# Connectors.net
KiCad netlist of a schematic drawn in Altium Designer
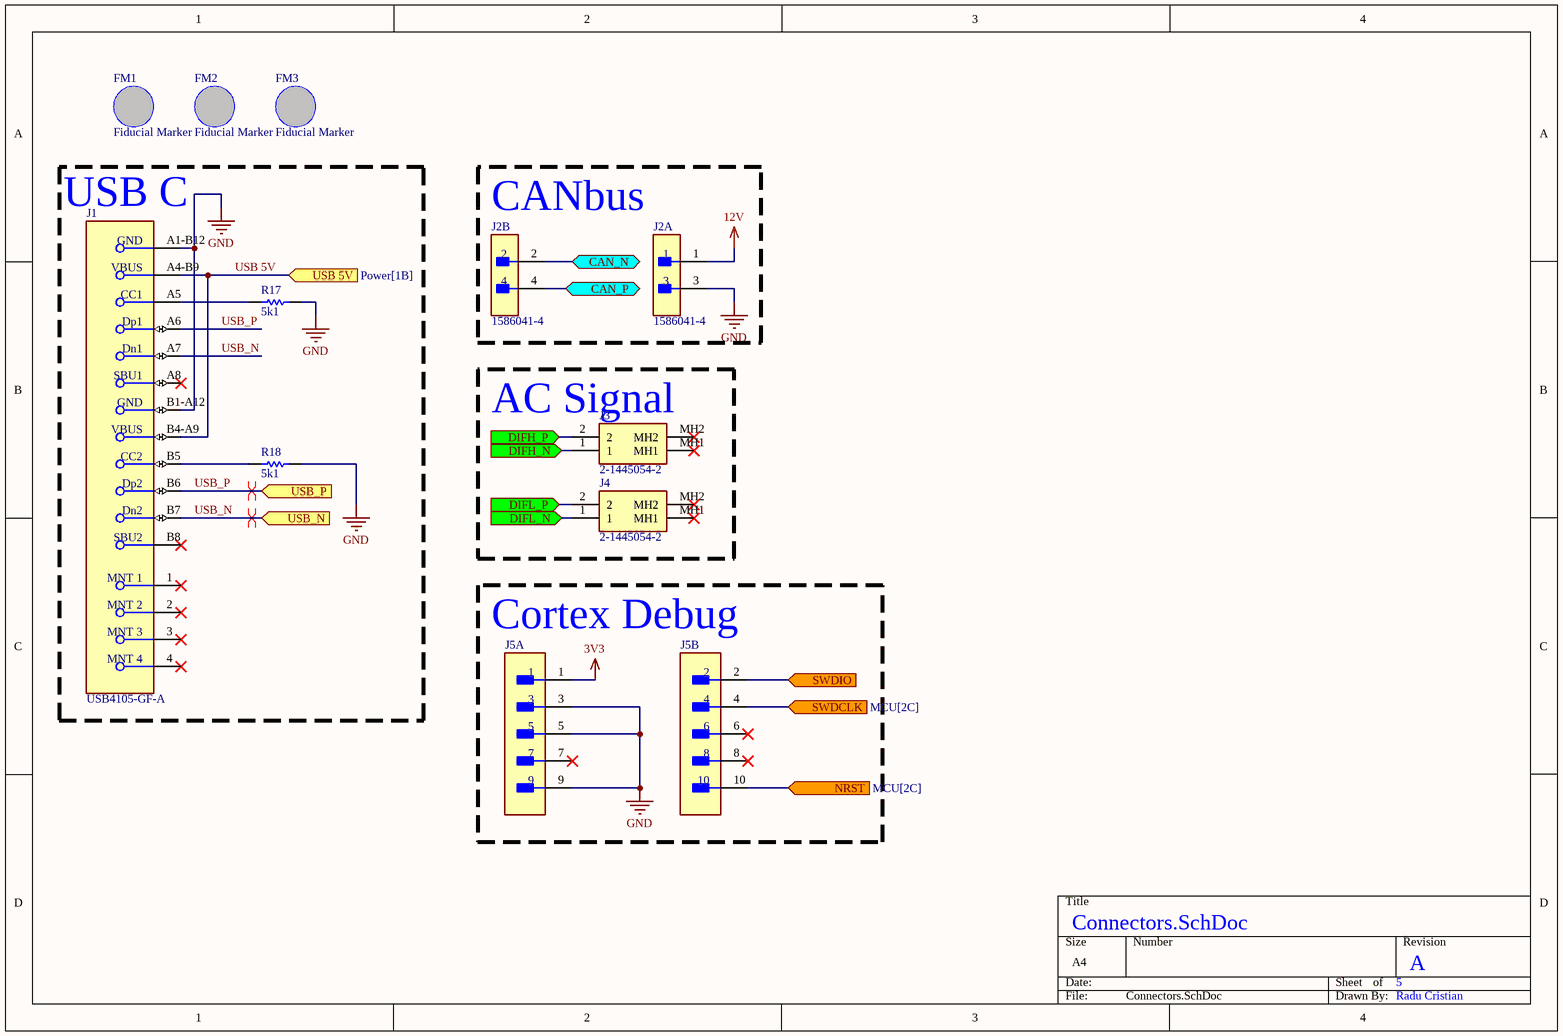
[diagram p0: Connectors.SchDoc]

(export (version "E")
  (design (tool "Eeschema 10.0.6"))
  (components
    (comp (ref "FM1")
      (value "Fiducial Marker")
      (footprint "Fiducial Marker-Footprint-1")
      (description "fancy style")
      (libsource (lib "ART-TU Cluj-Napoca") (part "FM?"))
    )
    (comp (ref "FM2")
      (value "Fiducial Marker")
      (footprint "Fiducial Marker-Footprint-1")
      (description "fancy style")
      (libsource (lib "ART-TU Cluj-Napoca") (part "FM?"))
    )
    (comp (ref "FM3")
      (value "Fiducial Marker")
      (footprint "Fiducial Marker-Footprint-1")
      (description "fancy style")
      (libsource (lib "ART-TU Cluj-Napoca") (part "FM?"))
    )
    (comp (ref "J1")
      (value "USB4105-GF-A")
      (footprint "FP-USB4105-GF-A-MFG")
      (description "CONN RCPT USB2.0 TYPEC 5A")
      (fields
        (field (name "MANUFACTURER") "GCT")
        (field (name "OCTOPART") "https://octopart.com/usb4105-gf-a-gct-106627878")
      )
      (libsource (lib "Altium Content Vault") (part "e7c17a616881a82b79941196b4bec10"))
    )
    (comp (ref "J2")
      (value "1586041-4")
      (footprint "FP-1586041-4-MFG")
      (description "CONN HEADER R/A 4POS 4.2MM")
      (fields
        (field (name "MANUFACTURER") "TE")
        (field (name "OCTOPART") "https://octopart.com/1586041-4-te+connectivity-46506786")
      )
      (libsource (lib "Altium Content Vault") (part "47a5dc621420b5f0973fcecc640382d"))
    )
    (comp (ref "J3")
      (value "2-1445054-2")
      (footprint "SamacSys:214450542")
      (description "Connector")
      (fields (field (name "MOUSER PART NUMBER") "571-2-1445054-2"))
      (libsource (lib "*") (part "2-1445054-2"))
    )
    (comp (ref "J4")
      (value "2-1445054-2")
      (footprint "SamacSys:214450542")
      (description "Connector")
      (fields (field (name "MOUSER PART NUMBER") "571-2-1445054-2"))
      (libsource (lib "*") (part "2-1445054-2"))
    )
    (comp (ref "J5")
      (value "FTSH-105-01-L-DV-K-P-TR")
      (footprint "FP-FTSH-105-01-L-DV-K-P-T-MFG")
      (description "CONN HEADER SMD 10POS 1.27MM")
      (libsource (lib "Altium Content Vault") (part "544f42128f4185dcb88ce1ce9bf1982"))
    )
    (comp (ref "R17")
      (value "RK73H2ATTD5101F")
      (footprint "RESC2013X60X30NL20T20")
      (fields (field (name "MANUFACTURER") "KOA Speer") (field (name "PARAMETER 1") "5k1"))
      (libsource (lib "Altium Content Vault") (part "RES"))
    )
    (comp (ref "R18")
      (value "RK73H2ATTD5101F")
      (footprint "RESC2013X60X30NL20T20")
      (fields (field (name "MANUFACTURER") "KOA Speer") (field (name "PARAMETER 1") "5k1"))
      (libsource (lib "Altium Content Vault") (part "RES"))
    )
  )
  (nets
    (net (code "1") (name "/CAN_N") (class "Default")
      (node (ref "J2") (pin "2") (pinfunction "2_2") (pintype "passive"))
    )
    (net (code "2") (name "/CAN_P") (class "Default")
      (node (ref "J2") (pin "4") (pinfunction "4_4") (pintype "passive"))
    )
    (net (code "3") (name "/DIFH_N") (class "Default")
      (node (ref "J3") (pin "1") (pinfunction "1_1") (pintype "passive"))
    )
    (net (code "4") (name "/DIFH_P") (class "Default")
      (node (ref "J3") (pin "2") (pinfunction "2_2") (pintype "passive"))
    )
    (net (code "5") (name "/DIFL_N") (class "Default")
      (node (ref "J4") (pin "1") (pinfunction "1_1") (pintype "passive"))
    )
    (net (code "6") (name "/DIFL_P") (class "Default")
      (node (ref "J4") (pin "2") (pinfunction "2_2") (pintype "passive"))
    )
    (net (code "7") (name "/NRST") (class "Default")
      (node (ref "J5") (pin "10") (pinfunction "10_10") (pintype "passive"))
    )
    (net (code "8") (name "/SWDCLK") (class "Default")
      (node (ref "J5") (pin "4") (pinfunction "4_4") (pintype "passive"))
    )
    (net (code "9") (name "/SWDIO") (class "Default")
      (node (ref "J5") (pin "2") (pinfunction "2_2") (pintype "passive"))
    )
    (net (code "10") (name "/USB 5V") (class "Default")
      (node (ref "J1") (pin "A4-B9") (pinfunction "VBUS_A4-B9") (pintype "power_in"))
      (node (ref "J1") (pin "B4-A9") (pinfunction "VBUS_B4-A9") (pintype "bidirectional"))
    )
    (net (code "11") (name "/USB_N") (class "Default")
      (node (ref "J1") (pin "A7") (pinfunction "Dn1_A7") (pintype "bidirectional"))
      (node (ref "J1") (pin "B7") (pinfunction "Dn2_B7") (pintype "bidirectional"))
    )
    (net (code "12") (name "/USB_P") (class "Default")
      (node (ref "J1") (pin "A6") (pinfunction "Dp1_A6") (pintype "bidirectional"))
      (node (ref "J1") (pin "B6") (pinfunction "Dp2_B6") (pintype "bidirectional"))
    )
    (net (code "13") (name "3V3") (class "Default")
      (node (ref "J5") (pin "1") (pinfunction "1_1") (pintype "passive"))
    )
    (net (code "14") (name "12V") (class "Default")
      (node (ref "J2") (pin "1") (pinfunction "1_1") (pintype "passive"))
    )
    (net (code "15") (name "GND") (class "Default")
      (node (ref "J1") (pin "A1-B12") (pinfunction "GND_A1-B12") (pintype "power_in"))
      (node (ref "J1") (pin "B1-A12") (pinfunction "GND_B1-A12") (pintype "bidirectional"))
      (node (ref "J2") (pin "3") (pinfunction "3_3") (pintype "passive"))
      (node (ref "J5") (pin "3") (pinfunction "3_3") (pintype "passive"))
      (node (ref "J5") (pin "5") (pinfunction "5_5") (pintype "passive"))
      (node (ref "J5") (pin "9") (pinfunction "9_9") (pintype "passive"))
      (node (ref "R17") (pin "1") (pinfunction "1_1") (pintype "passive"))
      (node (ref "R18") (pin "1") (pinfunction "1_1") (pintype "passive"))
    )
    (net (code "16") (name "Net-(J1-CC1)") (class "Default")
      (node (ref "J1") (pin "A5") (pinfunction "CC1_A5") (pintype "power_in"))
      (node (ref "R17") (pin "2") (pinfunction "2_2") (pintype "passive"))
    )
    (net (code "17") (name "Net-(J1-CC2)") (class "Default")
      (node (ref "J1") (pin "B5") (pinfunction "CC2_B5") (pintype "bidirectional"))
      (node (ref "R18") (pin "2") (pinfunction "2_2") (pintype "passive"))
    )
    (net (code "18") (name "unconnected-(J1-MNT_1-Pad1)") (class "Default")
      (node (ref "J1") (pin "1") (pinfunction "MNT_1_1") (pintype "power_in+no_connect"))
    )
    (net (code "19") (name "unconnected-(J1-MNT_2-Pad2)") (class "Default")
      (node (ref "J1") (pin "2") (pinfunction "MNT_2_2") (pintype "power_in+no_connect"))
    )
    (net (code "20") (name "unconnected-(J1-MNT_3-Pad3)") (class "Default")
      (node (ref "J1") (pin "3") (pinfunction "MNT_3_3") (pintype "power_in+no_connect"))
    )
    (net (code "21") (name "unconnected-(J1-MNT_4-Pad4)") (class "Default")
      (node (ref "J1") (pin "4") (pinfunction "MNT_4_4") (pintype "power_in+no_connect"))
    )
    (net (code "22") (name "unconnected-(J1-SBU1-PadA8)") (class "Default")
      (node (ref "J1") (pin "A8") (pinfunction "SBU1_A8") (pintype "bidirectional+no_connect"))
    )
    (net (code "23") (name "unconnected-(J1-SBU2-PadB8)") (class "Default")
      (node (ref "J1") (pin "B8") (pinfunction "SBU2_B8") (pintype "power_in+no_connect"))
    )
    (net (code "24") (name "unconnected-(J3-PadMH1)") (class "Default")
      (node (ref "J3") (pin "MH1") (pinfunction "MH1_MH1") (pintype "passive+no_connect"))
    )
    (net (code "25") (name "unconnected-(J3-PadMH2)") (class "Default")
      (node (ref "J3") (pin "MH2") (pinfunction "MH2_MH2") (pintype "passive+no_connect"))
    )
    (net (code "26") (name "unconnected-(J4-PadMH1)") (class "Default")
      (node (ref "J4") (pin "MH1") (pinfunction "MH1_MH1") (pintype "passive+no_connect"))
    )
    (net (code "27") (name "unconnected-(J4-PadMH2)") (class "Default")
      (node (ref "J4") (pin "MH2") (pinfunction "MH2_MH2") (pintype "passive+no_connect"))
    )
    (net (code "28") (name "unconnected-(J5-Pad6)") (class "Default")
      (node (ref "J5") (pin "6") (pinfunction "6_6") (pintype "passive+no_connect"))
    )
    (net (code "29") (name "unconnected-(J5-Pad7)") (class "Default")
      (node (ref "J5") (pin "7") (pinfunction "7_7") (pintype "passive+no_connect"))
    )
    (net (code "30") (name "unconnected-(J5-Pad8)") (class "Default")
      (node (ref "J5") (pin "8") (pinfunction "8_8") (pintype "passive+no_connect"))
    )
  )
)
